# Puzzle_-_Moisture_Sensor_v1_0.net
KiCad netlist of a schematic drawn in EAGLE
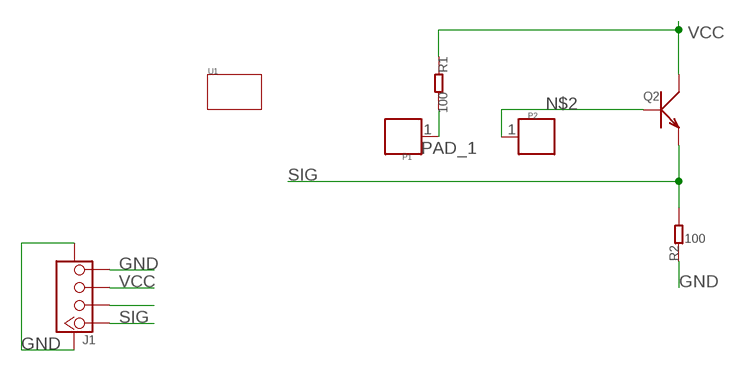
[diagram p0: schematic, sheet 1]

(export (version "E")
  (design (tool "Eeschema 10.0.6"))
  (components
    (comp (ref "J1")
      (value "TWIG-4P-2.0-SMD-FEMALE-REINFORCE'90D'")
      (footprint "eagle-import:4P-SMD-2.0-90D")
      (libsource (lib "eagle-import") (part "TWIG-4P-2.0-SMD-FEMALE-REINFORCE'90D'"))
    )
    (comp (ref "P1")
      (value "PAD.03")
      (footprint "eagle-import:1P-SMD-0.76X0.76")
      (libsource (lib "eagle-import") (part "PAD.03"))
    )
    (comp (ref "P2")
      (value "PAD.03")
      (footprint "eagle-import:1P-SMD-0.76X0.76")
      (libsource (lib "eagle-import") (part "PAD.03"))
    )
    (comp (ref "Q2")
      (value "TRANSISTOR-NPN-SOT23''")
      (footprint "eagle-import:SOT23")
      (libsource (lib "eagle-import") (part "TRANSISTOR-NPN-SOT23''"))
    )
    (comp (ref "R1")
      (value "100")
      (footprint "eagle-import:0603")
      (libsource (lib "eagle-import") (part "R-0603"))
    )
    (comp (ref "R2")
      (value "100")
      (footprint "eagle-import:0603")
      (libsource (lib "eagle-import") (part "R-0603"))
    )
    (comp (ref "U1")
      (value "TWIG'SPECIAL'")
      (footprint "eagle-import:3U-DIM-W_-DRILL-SPECIAL")
      (libsource (lib "eagle-import") (part "TWIG'SPECIAL'"))
    )
  )
  (nets
    (net (code "1") (name "/GND") (class "Default")
      (node (ref "J1") (pin "4") (pinfunction "4_4") (pintype "bidirectional"))
      (node (ref "J1") (pin "SS1") (pinfunction "SS1_SS1") (pintype "bidirectional"))
      (node (ref "J1") (pin "SS2") (pinfunction "SS2_SS2") (pintype "bidirectional"))
      (node (ref "R2") (pin "1") (pinfunction "1_1") (pintype "passive"))
    )
    (net (code "2") (name "/N$2") (class "Default")
      (node (ref "P2") (pin "1") (pinfunction "P$1_1") (pintype "bidirectional"))
      (node (ref "Q2") (pin "1") (pinfunction "B_1") (pintype "passive"))
    )
    (net (code "3") (name "/PAD_1") (class "Default")
      (node (ref "P1") (pin "1") (pinfunction "P$1_1") (pintype "bidirectional"))
      (node (ref "R1") (pin "2") (pinfunction "2_2") (pintype "passive"))
    )
    (net (code "4") (name "/SIG") (class "Default")
      (node (ref "J1") (pin "1") (pinfunction "1_1") (pintype "bidirectional"))
      (node (ref "Q2") (pin "2") (pinfunction "E_2") (pintype "passive"))
      (node (ref "R2") (pin "2") (pinfunction "2_2") (pintype "passive"))
    )
    (net (code "5") (name "/VCC") (class "Default")
      (node (ref "J1") (pin "3") (pinfunction "3_3") (pintype "bidirectional"))
      (node (ref "Q2") (pin "3") (pinfunction "C_3") (pintype "passive"))
      (node (ref "R1") (pin "1") (pinfunction "1_1") (pintype "passive"))
    )
    (net (code "6") (name "unconnected-(J1-Pad2)") (class "Default")
      (node (ref "J1") (pin "2") (pinfunction "2_2") (pintype "bidirectional"))
    )
  )
)
